# airball_sensor_board_v8_temp.net
KiCad netlist of a schematic drawn in EAGLE
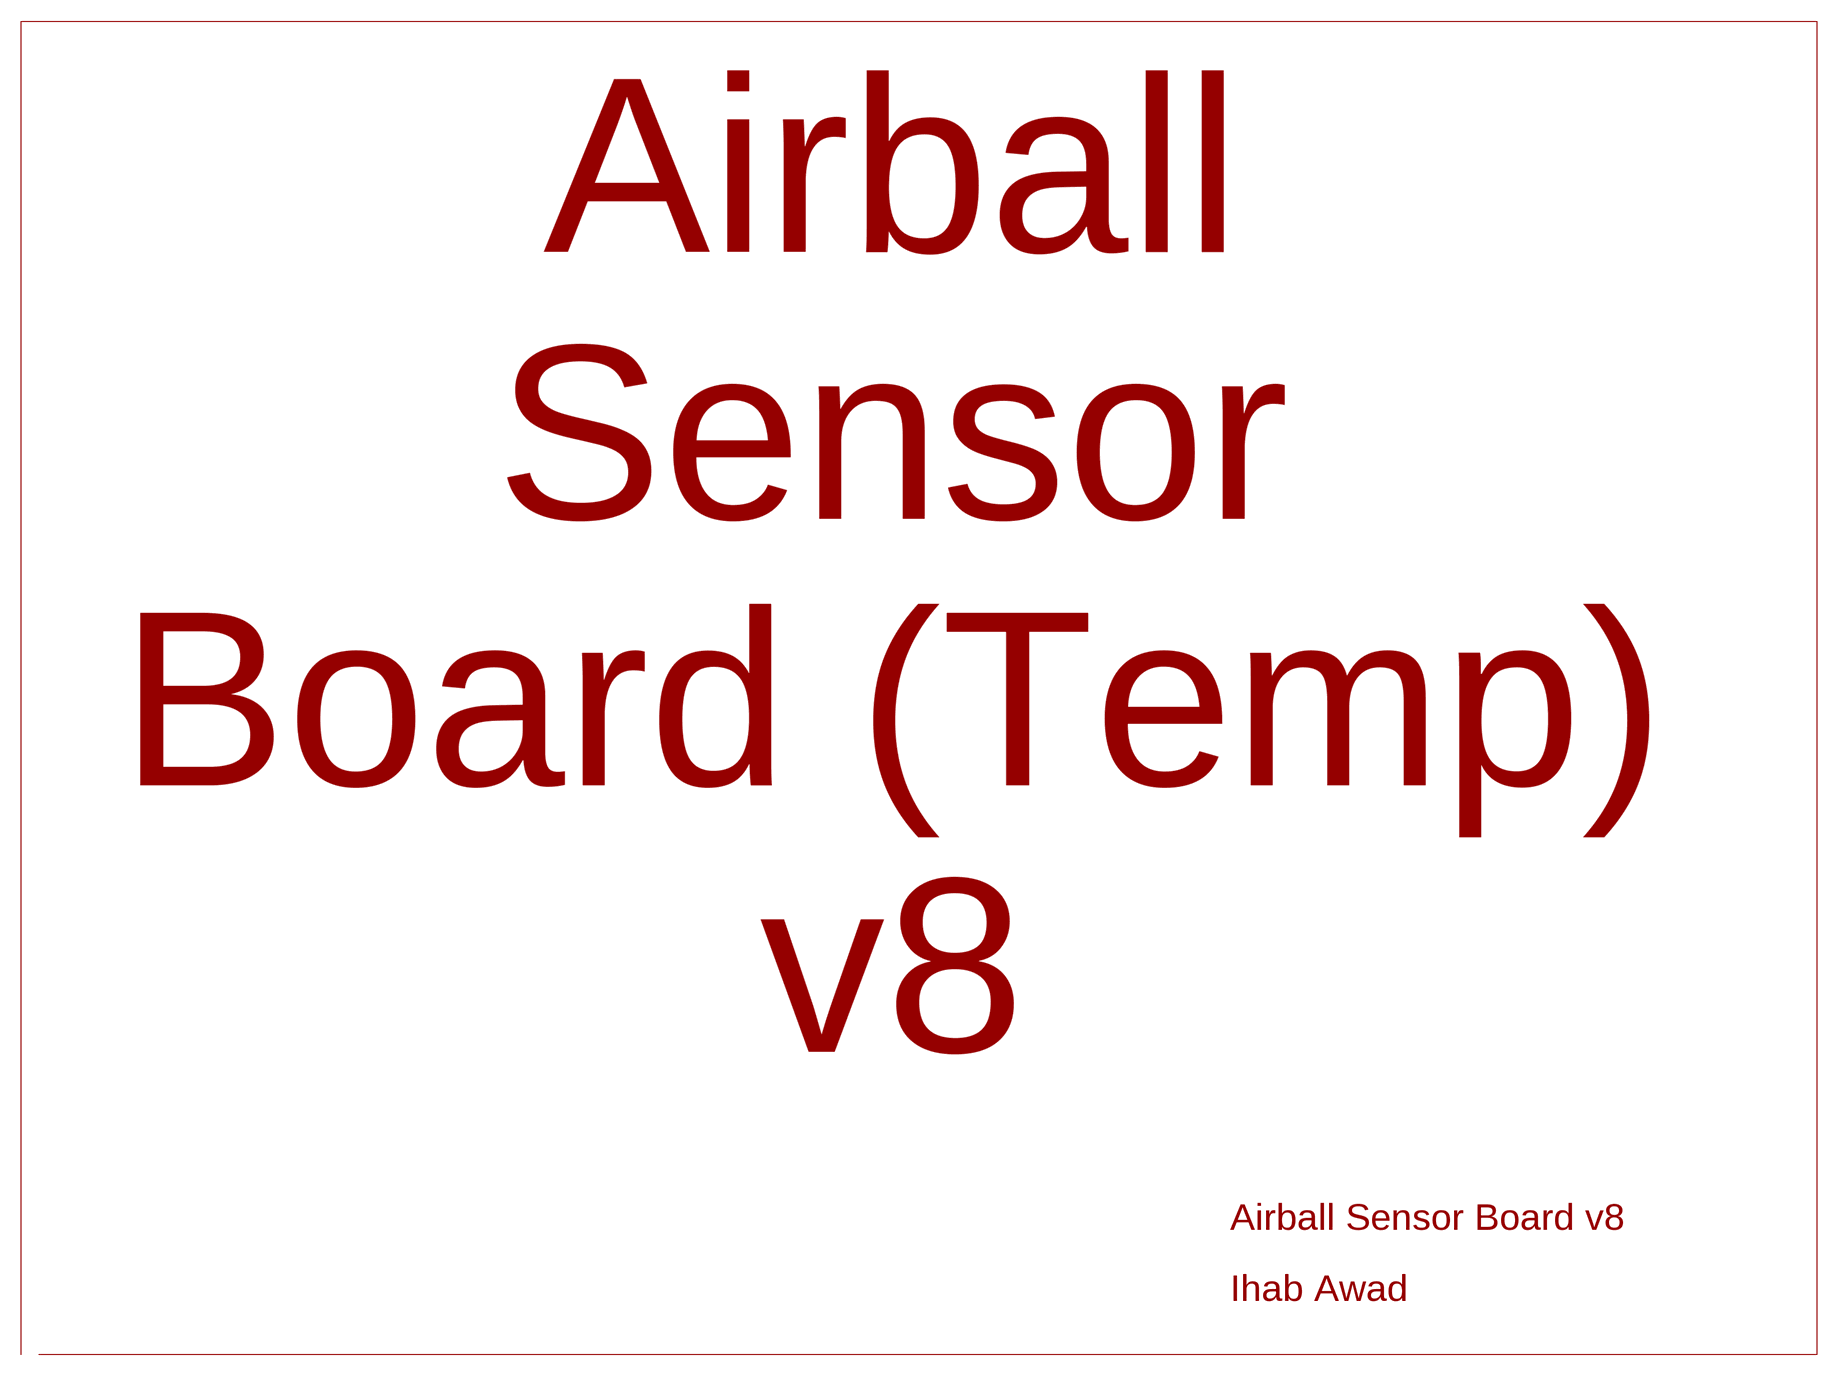
[diagram p0: schematic, sheet 1]
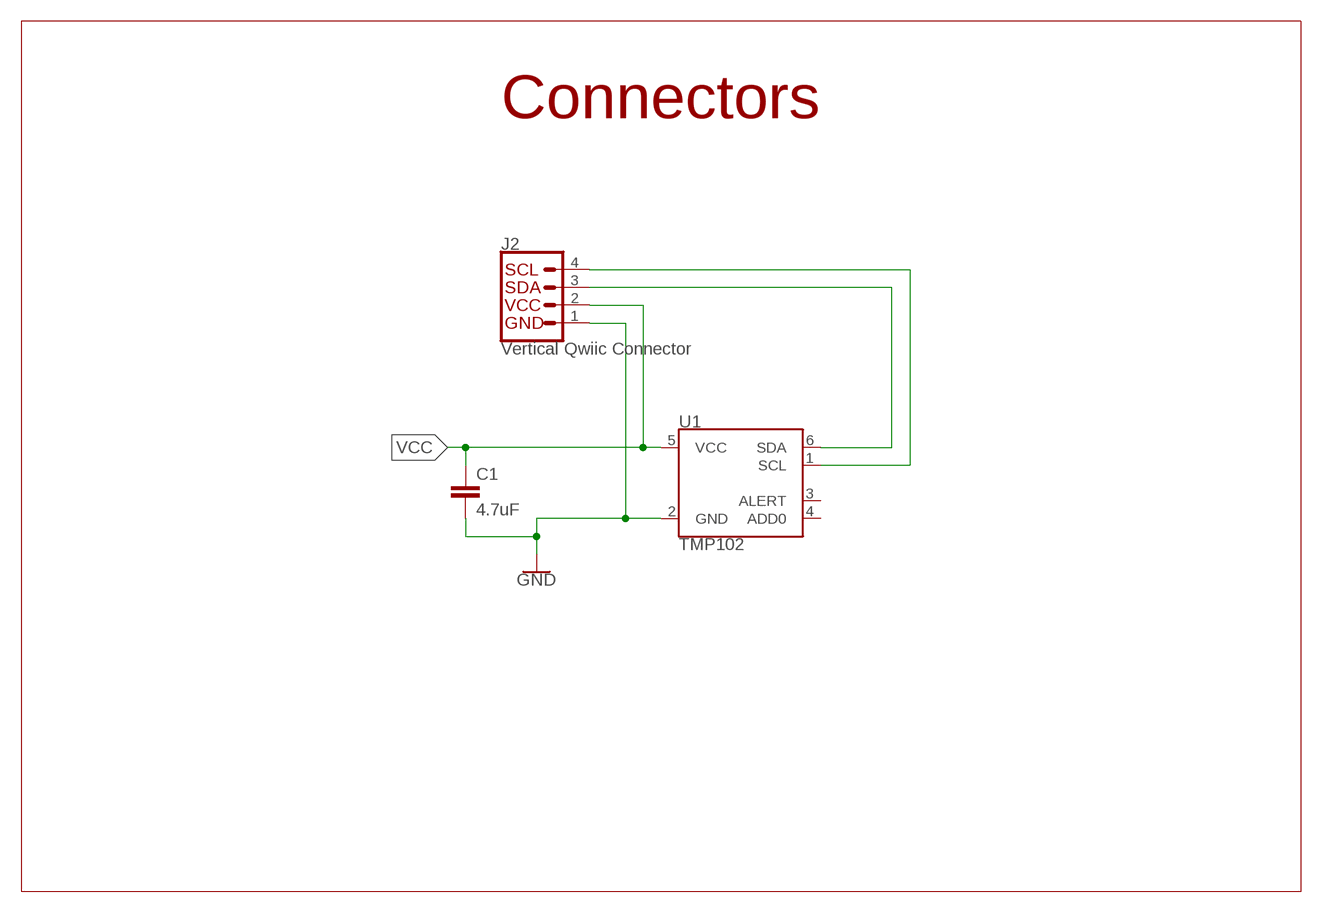
[diagram p1: schematic, sheet 2]

(export (version "E")
  (design (tool "Eeschema 10.0.6"))
  (components
    (comp (ref "C1")
      (value "4.7uF")
      (footprint "eagle-import:0603")
      (libsource (lib "eagle-import") (part "4.7UF-0603-6.3V-(10%)"))
    )
    (comp (ref "J2")
      (value "Vertical Qwiic Connector")
      (footprint "eagle-import:JST04_1MM_VERT")
      (libsource (lib "eagle-import") (part "QWIIC_CONNECTOR"))
    )
    (comp (ref "U1")
      (value "TMP102")
      (footprint "eagle-import:SOT563")
      (libsource (lib "eagle-import") (part "TMP102"))
    )
  )
  (nets
    (net (code "1") (name "GND") (class "Default")
      (node (ref "C1") (pin "2") (pinfunction "2_2") (pintype "passive"))
      (node (ref "J2") (pin "1") (pinfunction "1_1") (pintype "power_in"))
      (node (ref "U1") (pin "2") (pinfunction "GND_2") (pintype "bidirectional"))
    )
    (net (code "2") (name "Net-(U1-SCL)") (class "Default")
      (node (ref "J2") (pin "4") (pinfunction "4_4") (pintype "passive"))
      (node (ref "U1") (pin "1") (pinfunction "SCL_1") (pintype "bidirectional"))
    )
    (net (code "3") (name "Net-(U1-SDA)") (class "Default")
      (node (ref "J2") (pin "3") (pinfunction "3_3") (pintype "passive"))
      (node (ref "U1") (pin "6") (pinfunction "SDA_6") (pintype "bidirectional"))
    )
    (net (code "4") (name "VCC") (class "Default")
      (node (ref "C1") (pin "1") (pinfunction "1_1") (pintype "passive"))
      (node (ref "J2") (pin "2") (pinfunction "2_2") (pintype "power_in"))
      (node (ref "U1") (pin "5") (pinfunction "VCC_5") (pintype "bidirectional"))
    )
    (net (code "5") (name "unconnected-(U1-ADD0-Pad4)") (class "Default")
      (node (ref "U1") (pin "4") (pinfunction "ADD0_4") (pintype "bidirectional"))
    )
    (net (code "6") (name "unconnected-(U1-ALERT-Pad3)") (class "Default")
      (node (ref "U1") (pin "3") (pinfunction "ALERT_3") (pintype "bidirectional"))
    )
  )
)
